# Pad_V2.net
KiCad netlist of a schematic drawn in Altium Designer
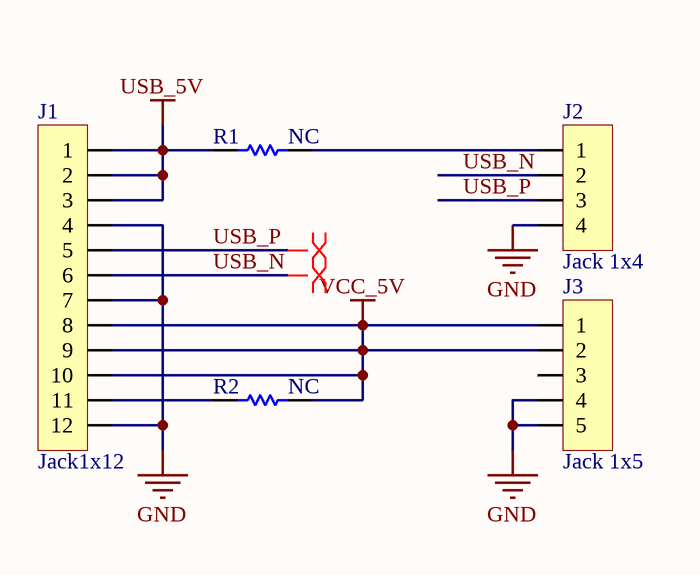
[diagram p0: 海关全向控制器Pad转接板V2.SchDoc]

(export (version "E")
  (design (tool "Eeschema 10.0.6"))
  (components
    (comp (ref "J1")
      (value "Jack1x12")
      (footprint "PPM.12-711-0102")
      (description "插座")
      (libsource (lib "Connector") (part "Jack1x12"))
    )
    (comp (ref "J2")
      (value "Jack 1x4")
      (footprint "ZH-4AWD")
      (description "插座")
      (libsource (lib "Connector") (part "Jack 1x4"))
    )
    (comp (ref "J3")
      (value "Jack 1x5")
      (footprint "ZH-5AWD")
      (description "插座")
      (libsource (lib "Connector") (part "Jack 1x5"))
    )
    (comp (ref "R1") (value "NC") (footprint "R0603") (libsource (lib "RLCYDF") (part "Res")))
    (comp (ref "R2") (value "NC") (footprint "R0603") (libsource (lib "RLCYDF") (part "Res")))
  )
  (nets
    (net (code "1") (name "/USB_N") (class "Default")
      (node (ref "J1") (pin "6") (pinfunction "6_6") (pintype "passive"))
      (node (ref "J2") (pin "2") (pinfunction "2_2") (pintype "passive"))
    )
    (net (code "2") (name "/USB_P") (class "Default")
      (node (ref "J1") (pin "5") (pinfunction "5_5") (pintype "passive"))
      (node (ref "J2") (pin "3") (pinfunction "3_3") (pintype "passive"))
    )
    (net (code "3") (name "GND") (class "Default")
      (node (ref "J1") (pin "12") (pinfunction "12_12") (pintype "passive"))
      (node (ref "J1") (pin "4") (pinfunction "4_4") (pintype "passive"))
      (node (ref "J1") (pin "7") (pinfunction "7_7") (pintype "passive"))
      (node (ref "J2") (pin "4") (pinfunction "4_4") (pintype "passive"))
      (node (ref "J3") (pin "4") (pinfunction "4_4") (pintype "passive"))
      (node (ref "J3") (pin "5") (pinfunction "5_5") (pintype "passive"))
    )
    (net (code "4") (name "Net-(J1-Pad11)") (class "Default")
      (node (ref "J1") (pin "11") (pinfunction "11_11") (pintype "passive"))
      (node (ref "R2") (pin "1") (pinfunction "1_1") (pintype "passive"))
    )
    (net (code "5") (name "Net-(J2-Pad1)") (class "Default")
      (node (ref "J2") (pin "1") (pinfunction "1_1") (pintype "passive"))
      (node (ref "R1") (pin "2") (pinfunction "2_2") (pintype "passive"))
    )
    (net (code "6") (name "USB_5V") (class "Default")
      (node (ref "J1") (pin "1") (pinfunction "1_1") (pintype "passive"))
      (node (ref "J1") (pin "2") (pinfunction "2_2") (pintype "passive"))
      (node (ref "J1") (pin "3") (pinfunction "3_3") (pintype "passive"))
      (node (ref "R1") (pin "1") (pinfunction "1_1") (pintype "passive"))
    )
    (net (code "7") (name "VCC_5V") (class "Default")
      (node (ref "J1") (pin "10") (pinfunction "10_10") (pintype "passive"))
      (node (ref "J1") (pin "8") (pinfunction "8_8") (pintype "passive"))
      (node (ref "J1") (pin "9") (pinfunction "9_9") (pintype "passive"))
      (node (ref "J3") (pin "1") (pinfunction "1_1") (pintype "passive"))
      (node (ref "J3") (pin "2") (pinfunction "2_2") (pintype "passive"))
      (node (ref "R2") (pin "2") (pinfunction "2_2") (pintype "passive"))
    )
    (net (code "8") (name "unconnected-(J3-Pad3)") (class "Default")
      (node (ref "J3") (pin "3") (pinfunction "3_3") (pintype "passive"))
    )
  )
)
